# mother_board.net
KiCad netlist of a schematic drawn in Altium Designer
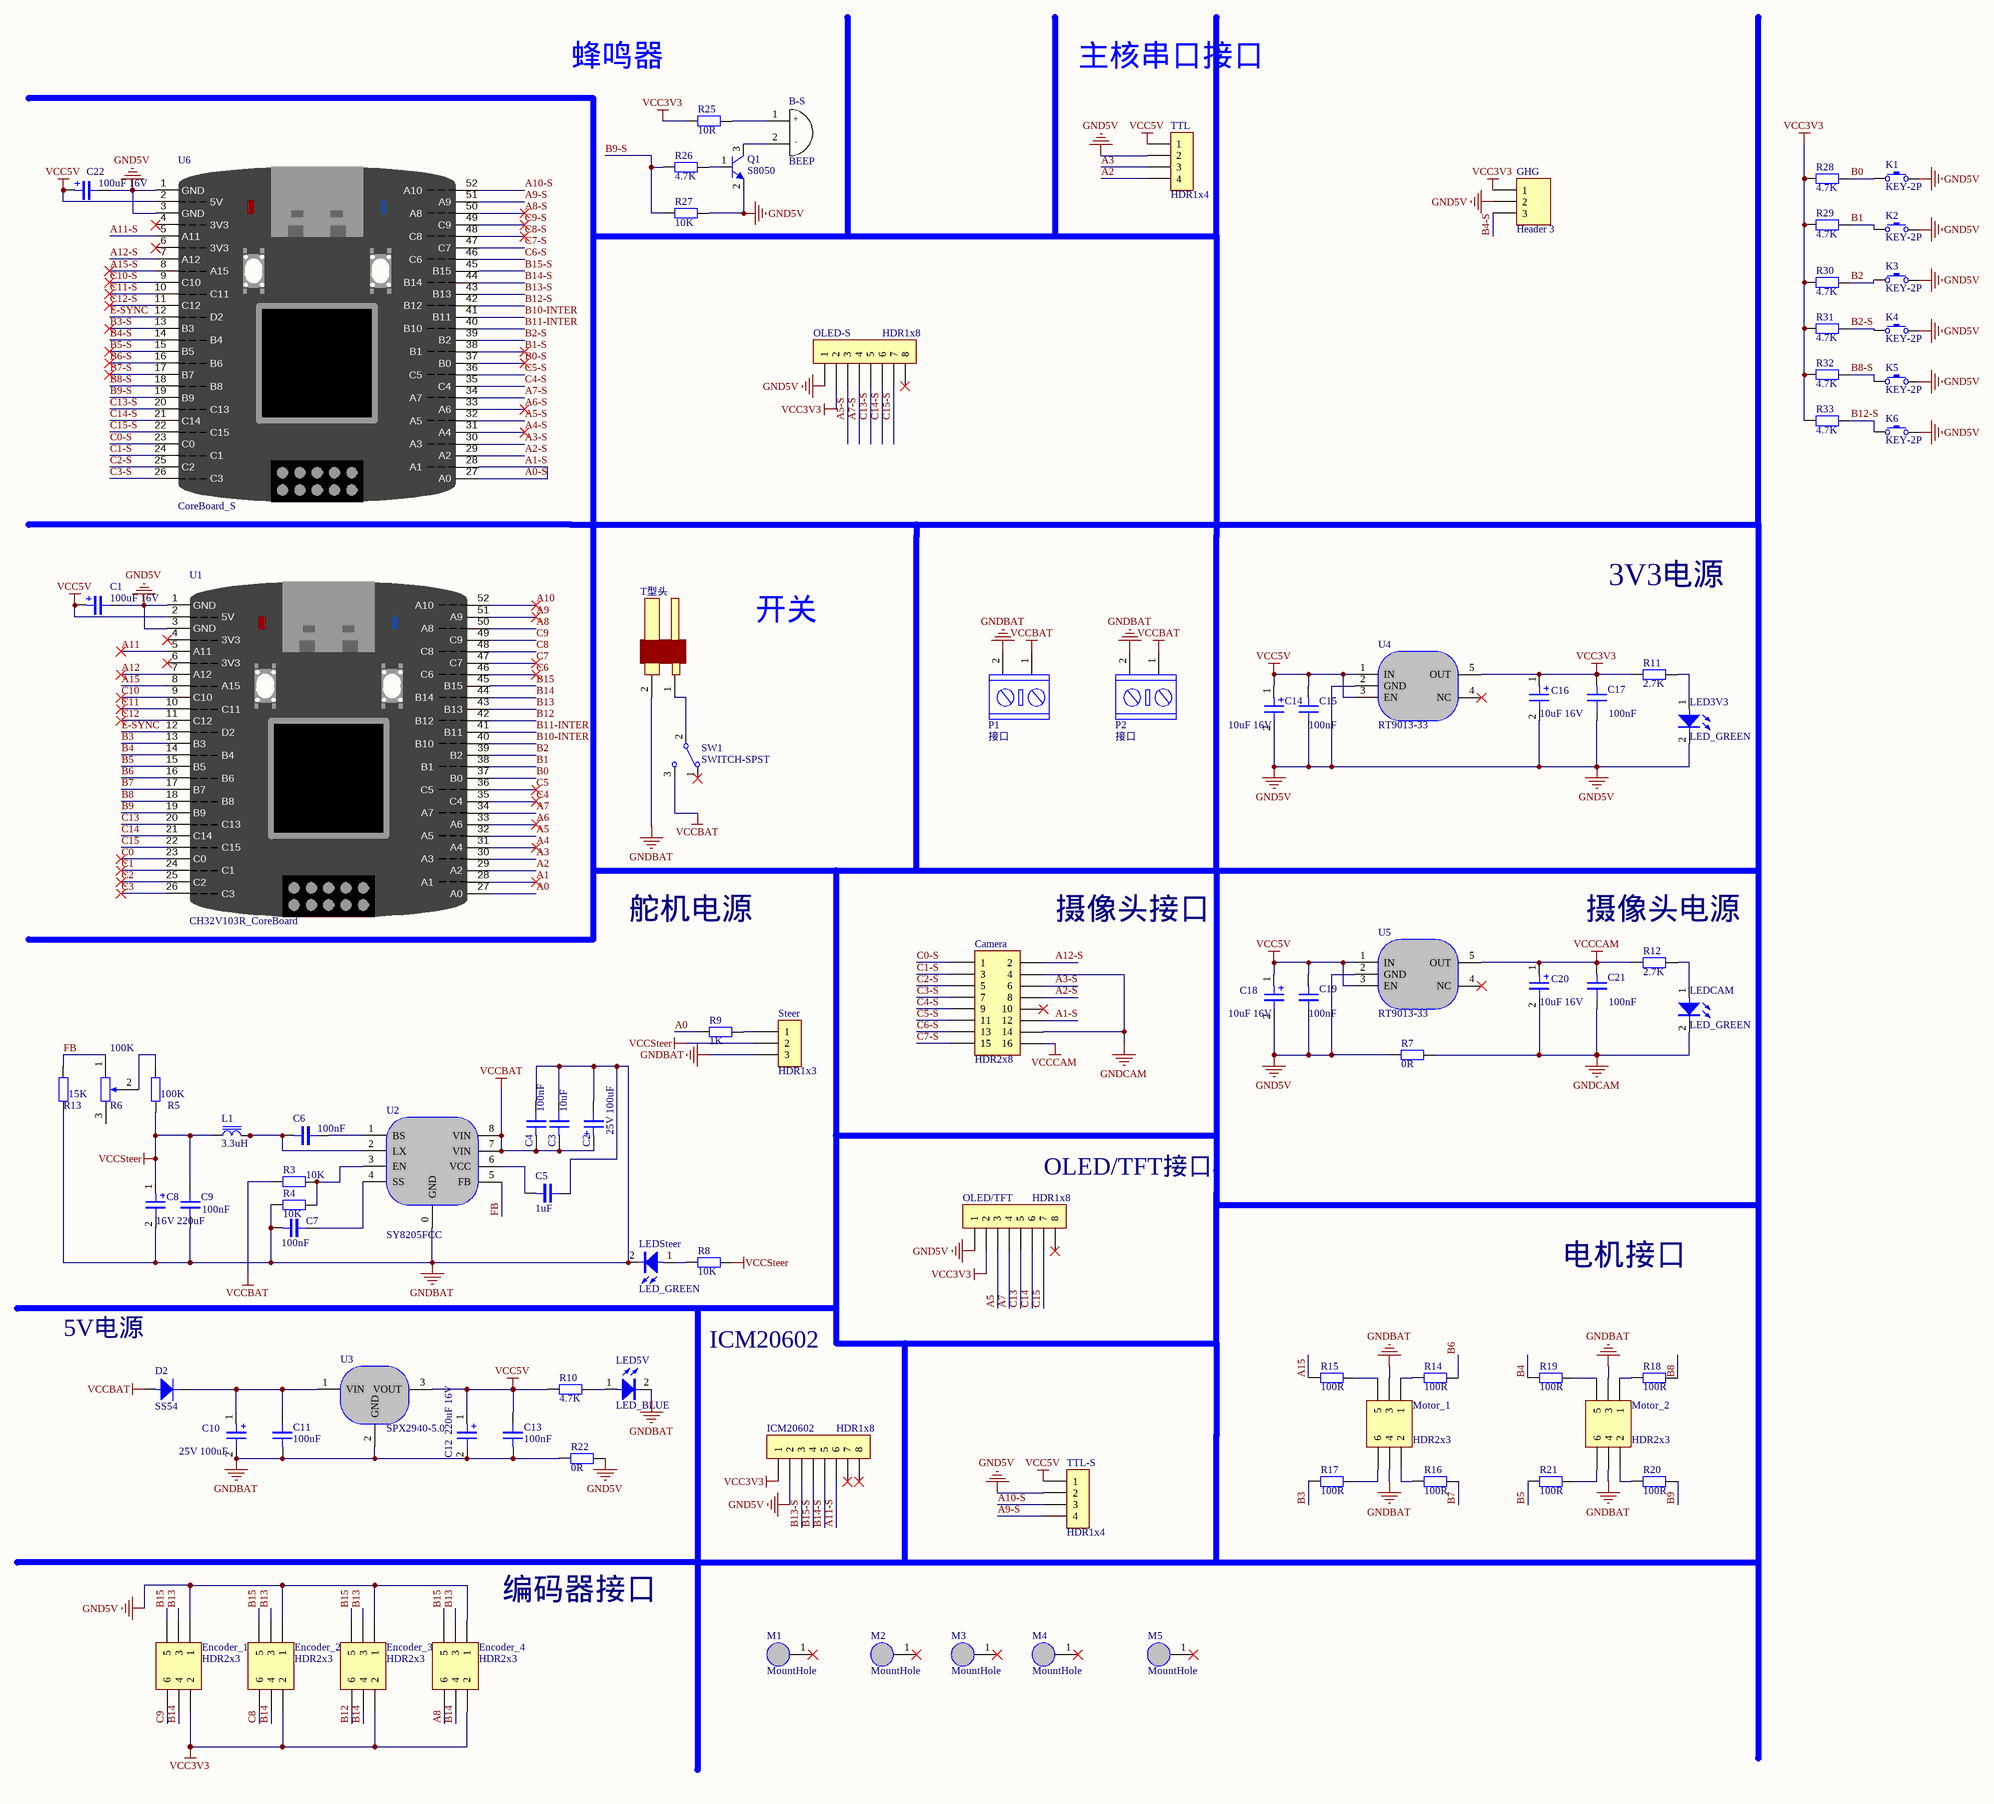
[diagram p0: mother_board.SchDoc]

(export (version "E")
  (design (tool "Eeschema 10.0.6"))
  (components
    (comp (ref "B-S")
      (value "BEEP")
      (footprint "BUZ-TH_BD9.0-P4.00-D1.0-FD")
      (libsource (lib "主板") (part "BEEP"))
    )
    (comp (ref "C1")
      (value "100uF 16V")
      (footprint "CASE-D_7343")
      (description "Tantalum Capacitor")
      (libsource (lib "主板") (part "CAP-TANTALUM"))
    )
    (comp (ref "C2")
      (value "25V 100uF")
      (footprint "SMD-ECAP-6.3x5.3")
      (description "Tantalum Capacitor")
      (libsource (lib "主板") (part "CAP-TANTALUM"))
    )
    (comp (ref "C3")
      (value "10uF")
      (footprint "0603_R")
      (description "Capacitor")
      (libsource (lib "主板") (part "CAP"))
    )
    (comp (ref "C4")
      (value "100nF")
      (footprint "0603_R")
      (description "Capacitor")
      (libsource (lib "主板") (part "CAP"))
    )
    (comp (ref "C5")
      (value "1uF")
      (footprint "0603_R")
      (description "Capacitor")
      (libsource (lib "主板") (part "CAP"))
    )
    (comp (ref "C6")
      (value "100nF")
      (footprint "0603_R")
      (description "Capacitor")
      (libsource (lib "主板") (part "CAP"))
    )
    (comp (ref "C7")
      (value "100nF")
      (footprint "0603_R")
      (description "Capacitor")
      (libsource (lib "主板") (part "CAP"))
    )
    (comp (ref "C8")
      (value "16V 220uF")
      (footprint "SMD-ECAP-6.3x5.3")
      (description "Tantalum Capacitor")
      (libsource (lib "") (part "CAP-TANTALUM_1"))
    )
    (comp (ref "C9")
      (value "100nF")
      (footprint "0603_R")
      (description "Capacitor")
      (libsource (lib "主板") (part "CAP"))
    )
    (comp (ref "C10")
      (value "25V 100uF")
      (footprint "SMD-ECAP-6.3x5.3")
      (description "Tantalum Capacitor")
      (libsource (lib "") (part "CAP-TANTALUM_1"))
    )
    (comp (ref "C11")
      (value "100nF")
      (footprint "0603_R")
      (description "Capacitor")
      (libsource (lib "主板") (part "CAP"))
    )
    (comp (ref "C12")
      (value "220uF 16V")
      (footprint "SMD-ECAP-6.3x5.3")
      (description "Tantalum Capacitor")
      (libsource (lib "") (part "CAP-TANTALUM_1"))
    )
    (comp (ref "C13")
      (value "100nF")
      (footprint "0603_R")
      (description "Capacitor")
      (libsource (lib "主板") (part "CAP"))
    )
    (comp (ref "C14")
      (value "10uF 16V")
      (footprint "CASE-A_3216")
      (description "Tantalum Capacitor")
      (libsource (lib "") (part "CAP-TANTALUM_1"))
    )
    (comp (ref "C15")
      (value "100nF")
      (footprint "0603_R")
      (description "Capacitor")
      (libsource (lib "主板") (part "CAP"))
    )
    (comp (ref "C16")
      (value "10uF 16V")
      (footprint "CASE-A_3216")
      (description "Tantalum Capacitor")
      (libsource (lib "") (part "CAP-TANTALUM_1"))
    )
    (comp (ref "C17")
      (value "100nF")
      (footprint "0603_R")
      (description "Capacitor")
      (libsource (lib "主板") (part "CAP"))
    )
    (comp (ref "C18")
      (value "10uF 16V")
      (footprint "CASE-A_3216")
      (description "Tantalum Capacitor")
      (libsource (lib "") (part "CAP-TANTALUM_1"))
    )
    (comp (ref "C19")
      (value "100nF")
      (footprint "0603_R")
      (description "Capacitor")
      (libsource (lib "主板") (part "CAP"))
    )
    (comp (ref "C20")
      (value "10uF 16V")
      (footprint "CASE-A_3216")
      (description "Tantalum Capacitor")
      (libsource (lib "") (part "CAP-TANTALUM_1"))
    )
    (comp (ref "C21")
      (value "100nF")
      (footprint "0603_R")
      (description "Capacitor")
      (libsource (lib "主板") (part "CAP"))
    )
    (comp (ref "C22")
      (value "100uF 16V")
      (footprint "CASE-D_7343")
      (description "Tantalum Capacitor")
      (libsource (lib "主板") (part "CAP-TANTALUM"))
    )
    (comp (ref "Camera")
      (value "HDR2x8")
      (footprint "HDR2X8")
      (description "Connector")
      (libsource (lib "主板") (part "HDR2x8"))
    )
    (comp (ref "D2")
      (value "SS54")
      (footprint "SMA(DO-214AC)_S1")
      (description "Schottky Diode")
      (libsource (lib "主板") (part "SS54"))
    )
    (comp (ref "Encoder_1")
      (value "HDR2x3")
      (footprint "HDR2X3")
      (description "Connector")
      (libsource (lib "主板") (part "HDR2x3"))
    )
    (comp (ref "Encoder_2")
      (value "HDR2x3")
      (footprint "HDR2X3")
      (description "Connector")
      (libsource (lib "主板") (part "HDR2x3"))
    )
    (comp (ref "Encoder_3")
      (value "HDR2x3")
      (footprint "HDR2X3")
      (description "Connector")
      (libsource (lib "主板") (part "HDR2x3"))
    )
    (comp (ref "Encoder_4")
      (value "HDR2x3")
      (footprint "HDR2X3")
      (description "Connector")
      (libsource (lib "主板") (part "HDR2x3"))
    )
    (comp (ref "GHG")
      (value "Header 3")
      (footprint "HDR1X3")
      (description "Header, 3-Pin")
      (fields (field (name "PUBLISHER") "Altium Limited"))
      (libsource (lib "Miscellaneous Connectors") (part "Header 3"))
    )
    (comp (ref "ICM20602")
      (value "HDR1x8")
      (footprint "HDR1X8")
      (description "Connector")
      (libsource (lib "主板") (part "HDR1x8"))
    )
    (comp (ref "K1")
      (value "KEY-2P")
      (footprint "SMD")
      (description "Key")
      (libsource (lib "主板") (part "KEY-2P"))
    )
    (comp (ref "K2")
      (value "KEY-2P")
      (footprint "SMD")
      (description "Key")
      (libsource (lib "主板") (part "KEY-2P"))
    )
    (comp (ref "K3")
      (value "KEY-2P")
      (footprint "SMD")
      (description "Key")
      (libsource (lib "主板") (part "KEY-2P"))
    )
    (comp (ref "K4")
      (value "KEY-2P")
      (footprint "SMD")
      (description "Key")
      (libsource (lib "主板") (part "KEY-2P"))
    )
    (comp (ref "K5")
      (value "KEY-2P")
      (footprint "SMD")
      (description "Key")
      (libsource (lib "主板") (part "KEY-2P"))
    )
    (comp (ref "K6")
      (value "KEY-2P")
      (footprint "SMD")
      (description "Key")
      (libsource (lib "主板") (part "KEY-2P"))
    )
    (comp (ref "L1") (value "3.3uH") (footprint "SMD-4.2x4.4x2.0") (libsource (lib "主板") (part "L?")))
    (comp (ref "LED3V3")
      (value "LED_GREEN")
      (footprint "0603-LED")
      (description "LED")
      (libsource (lib "主板") (part "LED"))
    )
    (comp (ref "LED5V")
      (value "LED_BLUE")
      (footprint "0603-LED")
      (description "LED")
      (libsource (lib "主板") (part "LED"))
    )
    (comp (ref "LEDCAM")
      (value "LED_GREEN")
      (footprint "0603-LED")
      (description "LED")
      (libsource (lib "主板") (part "LED"))
    )
    (comp (ref "LEDSteer")
      (value "LED_GREEN")
      (footprint "0603-LED")
      (description "LED")
      (libsource (lib "主板") (part "LED"))
    )
    (comp (ref "M1") (value "MountHole") (footprint "MountHole") (libsource (lib "主板") (part "MountHole")))
    (comp (ref "M2") (value "MountHole") (footprint "MountHole") (libsource (lib "主板") (part "MountHole")))
    (comp (ref "M3") (value "MountHole") (footprint "MountHole") (libsource (lib "主板") (part "MountHole")))
    (comp (ref "M4") (value "MountHole") (footprint "MountHole") (libsource (lib "主板") (part "MountHole")))
    (comp (ref "M5") (value "MountHole") (footprint "HOLE") (libsource (lib "主板") (part "MountHole")))
    (comp (ref "Motor_1")
      (value "HDR2x3")
      (footprint "HDR2X3")
      (description "Connector")
      (libsource (lib "主板") (part "HDR2x3"))
    )
    (comp (ref "Motor_2")
      (value "HDR2x3")
      (footprint "HDR2X3")
      (description "Connector")
      (libsource (lib "主板") (part "HDR2x3"))
    )
    (comp (ref "OLED-S")
      (value "HDR1x8")
      (footprint "HDR1X8")
      (description "Connector")
      (libsource (lib "主板") (part "HDR1x8"))
    )
    (comp (ref "OLED/TFT")
      (value "HDR1x8")
      (footprint "HDR1X8")
      (description "Connector")
      (libsource (lib "主板") (part "HDR1x8"))
    )
    (comp (ref "P1") (value "接口") (footprint "KF/WJ/DG 301-2p-5.0mm") (libsource (lib "主板") (part "接口")))
    (comp (ref "P2") (value "接口") (footprint "KF/WJ/DG 301-2p-5.0mm") (libsource (lib "主板") (part "接口")))
    (comp (ref "Q1")
      (value "S8050")
      (footprint "SOT-23(SOT-23-3)")
      (description "NPN Bipolar Transistor")
      (libsource (lib "主板") (part "S8050"))
    )
    (comp (ref "R3")
      (value "10K")
      (footprint "0603_L")
      (description "Resistor")
      (libsource (lib "主板") (part "RES"))
    )
    (comp (ref "R4")
      (value "10K")
      (footprint "0603_L")
      (description "Resistor")
      (libsource (lib "主板") (part "RES"))
    )
    (comp (ref "R5")
      (value "100K")
      (footprint "0603_L")
      (description "Resistor")
      (libsource (lib "") (part "RES_1"))
    )
    (comp (ref "R6")
      (value "100K")
      (footprint "3296W")
      (description "注意核对封装引脚")
      (libsource (lib "主板") (part "RES-CHANGABLE"))
    )
    (comp (ref "R7")
      (value "0R")
      (footprint "0603_L")
      (description "Resistor")
      (libsource (lib "主板") (part "RES"))
    )
    (comp (ref "R8")
      (value "10K")
      (footprint "0603_L")
      (description "Resistor")
      (libsource (lib "主板") (part "RES"))
    )
    (comp (ref "R9")
      (value "1K")
      (footprint "0603_L")
      (description "Resistor")
      (libsource (lib "主板") (part "RES"))
    )
    (comp (ref "R10")
      (value "4.7K")
      (footprint "0603_L")
      (description "Resistor")
      (libsource (lib "主板") (part "RES"))
    )
    (comp (ref "R11")
      (value "2.7K")
      (footprint "0603_L")
      (description "Resistor")
      (libsource (lib "主板") (part "RES"))
    )
    (comp (ref "R12")
      (value "2.7K")
      (footprint "0603_L")
      (description "Resistor")
      (libsource (lib "主板") (part "RES"))
    )
    (comp (ref "R13")
      (value "15K")
      (footprint "0603_L")
      (description "Resistor")
      (libsource (lib "") (part "RES_1"))
    )
    (comp (ref "R14")
      (value "100R")
      (footprint "0603_L")
      (description "Resistor")
      (libsource (lib "主板") (part "RES"))
    )
    (comp (ref "R15")
      (value "100R")
      (footprint "0603_L")
      (description "Resistor")
      (libsource (lib "主板") (part "RES"))
    )
    (comp (ref "R16")
      (value "100R")
      (footprint "0603_L")
      (description "Resistor")
      (libsource (lib "主板") (part "RES"))
    )
    (comp (ref "R17")
      (value "100R")
      (footprint "0603_L")
      (description "Resistor")
      (libsource (lib "主板") (part "RES"))
    )
    (comp (ref "R18")
      (value "100R")
      (footprint "0603_L")
      (description "Resistor")
      (libsource (lib "主板") (part "RES"))
    )
    (comp (ref "R19")
      (value "100R")
      (footprint "0603_L")
      (description "Resistor")
      (libsource (lib "主板") (part "RES"))
    )
    (comp (ref "R20")
      (value "100R")
      (footprint "0603_L")
      (description "Resistor")
      (libsource (lib "主板") (part "RES"))
    )
    (comp (ref "R21")
      (value "100R")
      (footprint "0603_L")
      (description "Resistor")
      (libsource (lib "主板") (part "RES"))
    )
    (comp (ref "R22")
      (value "0R")
      (footprint "0603_L")
      (description "Resistor")
      (libsource (lib "主板") (part "RES"))
    )
    (comp (ref "R25")
      (value "10R")
      (footprint "0603_L")
      (description "Resistor")
      (libsource (lib "主板") (part "RES"))
    )
    (comp (ref "R26")
      (value "4.7K")
      (footprint "0603_L")
      (description "Resistor")
      (libsource (lib "主板") (part "RES"))
    )
    (comp (ref "R27")
      (value "10K")
      (footprint "0603_L")
      (description "Resistor")
      (libsource (lib "主板") (part "RES"))
    )
    (comp (ref "R28")
      (value "4.7K")
      (footprint "0603_L")
      (description "Resistor")
      (libsource (lib "主板") (part "RES"))
    )
    (comp (ref "R29")
      (value "4.7K")
      (footprint "0603_L")
      (description "Resistor")
      (libsource (lib "主板") (part "RES"))
    )
    (comp (ref "R30")
      (value "4.7K")
      (footprint "0603_L")
      (description "Resistor")
      (libsource (lib "主板") (part "RES"))
    )
    (comp (ref "R31")
      (value "4.7K")
      (footprint "0603_L")
      (description "Resistor")
      (libsource (lib "主板") (part "RES"))
    )
    (comp (ref "R32")
      (value "4.7K")
      (footprint "0603_L")
      (description "Resistor")
      (libsource (lib "主板") (part "RES"))
    )
    (comp (ref "R33")
      (value "4.7K")
      (footprint "0603_L")
      (description "Resistor")
      (libsource (lib "主板") (part "RES"))
    )
    (comp (ref "Steer")
      (value "HDR1x3")
      (footprint "HDR1X3")
      (description "Connector")
      (libsource (lib "主板") (part "HDR1x3"))
    )
    (comp (ref "SW1")
      (value "SWITCH-SPST")
      (footprint "ToggleSwitch 7102")
      (description "Switch")
      (libsource (lib "主板") (part "SWITCH-SPST"))
    )
    (comp (ref "TTL")
      (value "HDR1x4")
      (footprint "HDR1X4")
      (description "Connector")
      (libsource (lib "主板") (part "HDR1x4"))
    )
    (comp (ref "TTL-S")
      (value "HDR1x4")
      (footprint "HDR1X4")
      (description "Connector")
      (libsource (lib "主板") (part "HDR1x4"))
    )
    (comp (ref "T型头") (value "T型头") (footprint "T型头焊盘") (libsource (lib "主板") (part "T型头")))
    (comp (ref "U1")
      (value "CH32V103R_CoreBoard")
      (footprint "CH32V103R_CoreBoard")
      (description "逐飞科技 CH32V103R核心板")
      (libsource (lib "主板") (part "CH32V103R_CoreBoard"))
    )
    (comp (ref "U2")
      (value "SY8205FCC")
      (footprint "SOIC-8_EP_150mil")
      (libsource (lib "主板") (part "SY8205FCC"))
    )
    (comp (ref "U3") (value "SPX2940-5.0") (footprint "TO-263-3") (libsource (lib "主板") (part "SPX2940-5.0")))
    (comp (ref "U4") (value "RT9013-33") (footprint "SOT-23-5") (libsource (lib "主板") (part "RT9013-33")))
    (comp (ref "U5") (value "RT9013-33") (footprint "SOT-23-5") (libsource (lib "主板") (part "RT9013-33")))
    (comp (ref "U6")
      (value "CoreBoard_S")
      (footprint "CH32V103R_CoreBoard")
      (description "逐飞科技 CH32V103R核心板")
      (libsource (lib "主板") (part "CH32V103R_CoreBoard"))
    )
  )
  (nets
    (net (code "1") (name "/A0") (class "Default")
      (node (ref "R9") (pin "1") (pinfunction "1_1") (pintype "passive"))
      (node (ref "U1") (pin "27") (pinfunction "A0_27") (pintype "passive"))
    )
    (net (code "2") (name "/A0-S") (class "Default")
      (node (ref "Camera") (pin "12") (pinfunction "12_12") (pintype "passive"))
      (node (ref "U6") (pin "27") (pinfunction "A0_27") (pintype "passive"))
      (node (ref "U6") (pin "28") (pinfunction "A1_28") (pintype "passive"))
    )
    (net (code "3") (name "/A1") (class "Default")
      (node (ref "U1") (pin "28") (pinfunction "A1_28") (pintype "passive+no_connect"))
    )
    (net (code "4") (name "/A2") (class "Default")
      (node (ref "TTL") (pin "4") (pinfunction "4_4") (pintype "passive"))
      (node (ref "U1") (pin "29") (pinfunction "A2_29") (pintype "passive"))
    )
    (net (code "5") (name "/A2-S") (class "Default")
      (node (ref "Camera") (pin "8") (pinfunction "8_8") (pintype "passive"))
      (node (ref "U6") (pin "29") (pinfunction "A2_29") (pintype "passive"))
    )
    (net (code "6") (name "/A3") (class "Default")
      (node (ref "TTL") (pin "3") (pinfunction "3_3") (pintype "passive"))
      (node (ref "U1") (pin "30") (pinfunction "A3_30") (pintype "passive"))
    )
    (net (code "7") (name "/A3-S") (class "Default")
      (node (ref "Camera") (pin "6") (pinfunction "6_6") (pintype "passive"))
      (node (ref "U6") (pin "30") (pinfunction "A3_30") (pintype "passive"))
    )
    (net (code "8") (name "/A4") (class "Default")
      (node (ref "U1") (pin "31") (pinfunction "A4_31") (pintype "passive+no_connect"))
    )
    (net (code "9") (name "/A4-S") (class "Default")
      (node (ref "U6") (pin "31") (pinfunction "A4_31") (pintype "passive+no_connect"))
    )
    (net (code "10") (name "/A5") (class "Default")
      (node (ref "OLED/TFT") (pin "3") (pinfunction "3_3") (pintype "passive"))
      (node (ref "U1") (pin "32") (pinfunction "A5_32") (pintype "passive"))
    )
    (net (code "11") (name "/A5-S") (class "Default")
      (node (ref "OLED-S") (pin "3") (pinfunction "3_3") (pintype "passive"))
      (node (ref "U6") (pin "32") (pinfunction "A5_32") (pintype "passive"))
    )
    (net (code "12") (name "/A6") (class "Default")
      (node (ref "U1") (pin "33") (pinfunction "A6_33") (pintype "passive+no_connect"))
    )
    (net (code "13") (name "/A6-S") (class "Default")
      (node (ref "U6") (pin "33") (pinfunction "A6_33") (pintype "passive+no_connect"))
    )
    (net (code "14") (name "/A7") (class "Default")
      (node (ref "OLED/TFT") (pin "4") (pinfunction "4_4") (pintype "passive"))
      (node (ref "U1") (pin "34") (pinfunction "A7_34") (pintype "passive"))
    )
    (net (code "15") (name "/A7-S") (class "Default")
      (node (ref "OLED-S") (pin "4") (pinfunction "4_4") (pintype "passive"))
      (node (ref "U6") (pin "34") (pinfunction "A7_34") (pintype "passive"))
    )
    (net (code "16") (name "/A8") (class "Default")
      (node (ref "Encoder_4") (pin "6") (pinfunction "6_6") (pintype "passive"))
      (node (ref "U1") (pin "50") (pinfunction "A8_50") (pintype "passive"))
    )
    (net (code "17") (name "/A8-S") (class "Default")
      (node (ref "U6") (pin "50") (pinfunction "A8_50") (pintype "passive+no_connect"))
    )
    (net (code "18") (name "/A9") (class "Default")
      (node (ref "U1") (pin "51") (pinfunction "A9_51") (pintype "passive+no_connect"))
    )
    (net (code "19") (name "/A9-S") (class "Default")
      (node (ref "TTL-S") (pin "4") (pinfunction "4_4") (pintype "passive"))
      (node (ref "U6") (pin "51") (pinfunction "A9_51") (pintype "passive"))
    )
    (net (code "20") (name "/A10") (class "Default")
      (node (ref "U1") (pin "52") (pinfunction "A10_52") (pintype "passive+no_connect"))
    )
    (net (code "21") (name "/A10-S") (class "Default")
      (node (ref "TTL-S") (pin "3") (pinfunction "3_3") (pintype "passive"))
      (node (ref "U6") (pin "52") (pinfunction "A10_52") (pintype "passive"))
    )
    (net (code "22") (name "/A11") (class "Default")
      (node (ref "U1") (pin "5") (pinfunction "A11_5") (pintype "passive+no_connect"))
    )
    (net (code "23") (name "/A11-S") (class "Default")
      (node (ref "ICM20602") (pin "6") (pinfunction "6_6") (pintype "passive"))
      (node (ref "U6") (pin "5") (pinfunction "A11_5") (pintype "passive"))
    )
    (net (code "24") (name "/A12") (class "Default")
      (node (ref "U1") (pin "7") (pinfunction "A12_7") (pintype "passive+no_connect"))
    )
    (net (code "25") (name "/A12-S") (class "Default")
      (node (ref "Camera") (pin "2") (pinfunction "2_2") (pintype "passive"))
      (node (ref "U6") (pin "7") (pinfunction "A12_7") (pintype "passive"))
    )
    (net (code "26") (name "/A15") (class "Default")
      (node (ref "R15") (pin "1") (pinfunction "1_1") (pintype "passive"))
      (node (ref "U1") (pin "8") (pinfunction "A15_8") (pintype "passive"))
    )
    (net (code "27") (name "/A15-S") (class "Default")
      (node (ref "U6") (pin "8") (pinfunction "A15_8") (pintype "passive+no_connect"))
    )
    (net (code "28") (name "/B0") (class "Default")
      (node (ref "K1") (pin "1") (pinfunction "1_1") (pintype "passive"))
      (node (ref "R28") (pin "2") (pinfunction "2_2") (pintype "passive"))
      (node (ref "U1") (pin "37") (pinfunction "B0_37") (pintype "passive"))
    )
    (net (code "29") (name "/B0-S") (class "Default")
      (node (ref "U6") (pin "37") (pinfunction "B0_37") (pintype "passive+no_connect"))
    )
    (net (code "30") (name "/B1") (class "Default")
      (node (ref "K2") (pin "1") (pinfunction "1_1") (pintype "passive"))
      (node (ref "R29") (pin "2") (pinfunction "2_2") (pintype "passive"))
      (node (ref "U1") (pin "38") (pinfunction "B1_38") (pintype "passive"))
    )
    (net (code "31") (name "/B1-S") (class "Default")
      (node (ref "U6") (pin "38") (pinfunction "B1_38") (pintype "passive+no_connect"))
    )
    (net (code "32") (name "/B2") (class "Default")
      (node (ref "K3") (pin "1") (pinfunction "1_1") (pintype "passive"))
      (node (ref "R30") (pin "2") (pinfunction "2_2") (pintype "passive"))
      (node (ref "U1") (pin "39") (pinfunction "B2_39") (pintype "passive"))
    )
    (net (code "33") (name "/B2-S") (class "Default")
      (node (ref "K4") (pin "1") (pinfunction "1_1") (pintype "passive"))
      (node (ref "R31") (pin "2") (pinfunction "2_2") (pintype "passive"))
      (node (ref "U6") (pin "39") (pinfunction "B2_39") (pintype "passive"))
    )
    (net (code "34") (name "/B3") (class "Default")
      (node (ref "R17") (pin "1") (pinfunction "1_1") (pintype "passive"))
      (node (ref "U1") (pin "13") (pinfunction "B3_13") (pintype "passive"))
    )
    (net (code "35") (name "/B3-S") (class "Default")
      (node (ref "U6") (pin "13") (pinfunction "B3_13") (pintype "passive+no_connect"))
    )
    (net (code "36") (name "/B4") (class "Default")
      (node (ref "R19") (pin "1") (pinfunction "1_1") (pintype "passive"))
      (node (ref "U1") (pin "14") (pinfunction "B4_14") (pintype "passive"))
    )
    (net (code "37") (name "/B4-S") (class "Default")
      (node (ref "GHG") (pin "3") (pinfunction "3_3") (pintype "passive"))
      (node (ref "U6") (pin "14") (pinfunction "B4_14") (pintype "passive"))
    )
    (net (code "38") (name "/B5") (class "Default")
      (node (ref "R21") (pin "1") (pinfunction "1_1") (pintype "passive"))
      (node (ref "U1") (pin "15") (pinfunction "B5_15") (pintype "passive"))
    )
    (net (code "39") (name "/B5-S") (class "Default")
      (node (ref "U6") (pin "15") (pinfunction "B5_15") (pintype "passive+no_connect"))
    )
    (net (code "40") (name "/B6") (class "Default")
      (node (ref "R14") (pin "2") (pinfunction "2_2") (pintype "passive"))
      (node (ref "U1") (pin "16") (pinfunction "B6_16") (pintype "passive"))
    )
    (net (code "41") (name "/B6-S") (class "Default")
      (node (ref "U6") (pin "16") (pinfunction "B6_16") (pintype "passive+no_connect"))
    )
    (net (code "42") (name "/B7") (class "Default")
      (node (ref "R16") (pin "2") (pinfunction "2_2") (pintype "passive"))
      (node (ref "U1") (pin "17") (pinfunction "B7_17") (pintype "passive"))
    )
    (net (code "43") (name "/B7-S") (class "Default")
      (node (ref "U6") (pin "17") (pinfunction "B7_17") (pintype "passive+no_connect"))
    )
    (net (code "44") (name "/B8") (class "Default")
      (node (ref "R18") (pin "2") (pinfunction "2_2") (pintype "passive"))
      (node (ref "U1") (pin "18") (pinfunction "B8_18") (pintype "passive"))
    )
    (net (code "45") (name "/B8-S") (class "Default")
      (node (ref "K5") (pin "1") (pinfunction "1_1") (pintype "passive"))
      (node (ref "R32") (pin "2") (pinfunction "2_2") (pintype "passive"))
      (node (ref "U6") (pin "18") (pinfunction "B8_18") (pintype "passive"))
    )
    (net (code "46") (name "/B9") (class "Default")
      (node (ref "R20") (pin "2") (pinfunction "2_2") (pintype "passive"))
      (node (ref "U1") (pin "19") (pinfunction "B9_19") (pintype "passive"))
    )
    (net (code "47") (name "/B9-S") (class "Default")
      (node (ref "R26") (pin "1") (pinfunction "1_1") (pintype "passive"))
      (node (ref "R27") (pin "1") (pinfunction "1_1") (pintype "passive"))
      (node (ref "U6") (pin "19") (pinfunction "B9_19") (pintype "passive"))
    )
    (net (code "48") (name "/B10-INTER") (class "Default")
      (node (ref "U1") (pin "40") (pinfunction "B10_40") (pintype "passive"))
      (node (ref "U6") (pin "41") (pinfunction "B11_41") (pintype "passive"))
    )
    (net (code "49") (name "/B11-INTER") (class "Default")
      (node (ref "U1") (pin "41") (pinfunction "B11_41") (pintype "passive"))
      (node (ref "U6") (pin "40") (pinfunction "B10_40") (pintype "passive"))
    )
    (net (code "50") (name "/B12") (class "Default")
      (node (ref "Encoder_3") (pin "6") (pinfunction "6_6") (pintype "passive"))
      (node (ref "U1") (pin "42") (pinfunction "B12_42") (pintype "passive"))
    )
    (net (code "51") (name "/B12-S") (class "Default")
      (node (ref "K6") (pin "1") (pinfunction "1_1") (pintype "passive"))
      (node (ref "R33") (pin "2") (pinfunction "2_2") (pintype "passive"))
      (node (ref "U6") (pin "42") (pinfunction "B12_42") (pintype "passive"))
    )
    (net (code "52") (name "/B13") (class "Default")
      (node (ref "Encoder_1") (pin "3") (pinfunction "3_3") (pintype "passive"))
      (node (ref "Encoder_2") (pin "3") (pinfunction "3_3") (pintype "passive"))
      (node (ref "Encoder_3") (pin "3") (pinfunction "3_3") (pintype "passive"))
      (node (ref "Encoder_4") (pin "3") (pinfunction "3_3") (pintype "passive"))
      (node (ref "U1") (pin "43") (pinfunction "B13_43") (pintype "passive"))
    )
    (net (code "53") (name "/B13-S") (class "Default")
      (node (ref "ICM20602") (pin "3") (pinfunction "3_3") (pintype "passive"))
      (node (ref "U6") (pin "43") (pinfunction "B13_43") (pintype "passive"))
    )
    (net (code "54") (name "/B14") (class "Default")
      (node (ref "Encoder_1") (pin "4") (pinfunction "4_4") (pintype "passive"))
      (node (ref "Encoder_2") (pin "4") (pinfunction "4_4") (pintype "passive"))
      (node (ref "Encoder_3") (pin "4") (pinfunction "4_4") (pintype "passive"))
      (node (ref "Encoder_4") (pin "4") (pinfunction "4_4") (pintype "passive"))
      (node (ref "U1") (pin "44") (pinfunction "B14_44") (pintype "passive"))
    )
    (net (code "55") (name "/B14-S") (class "Default")
      (node (ref "ICM20602") (pin "5") (pinfunction "5_5") (pintype "passive"))
      (node (ref "U6") (pin "44") (pinfunction "B14_44") (pintype "passive"))
    )
    (net (code "56") (name "/B15") (class "Default")
      (node (ref "Encoder_1") (pin "5") (pinfunction "5_5") (pintype "passive"))
      (node (ref "Encoder_2") (pin "5") (pinfunction "5_5") (pintype "passive"))
      (node (ref "Encoder_3") (pin "5") (pinfunction "5_5") (pintype "passive"))
      (node (ref "Encoder_4") (pin "5") (pinfunction "5_5") (pintype "passive"))
      (node (ref "U1") (pin "45") (pinfunction "B15_45") (pintype "passive"))
    )
    (net (code "57") (name "/B15-S") (class "Default")
      (node (ref "ICM20602") (pin "4") (pinfunction "4_4") (pintype "passive"))
      (node (ref "U6") (pin "45") (pinfunction "B15_45") (pintype "passive"))
    )
    (net (code "58") (name "/C0") (class "Default")
      (node (ref "U1") (pin "23") (pinfunction "C0_23") (pintype "passive+no_connect"))
    )
    (net (code "59") (name "/C0-S") (class "Default")
      (node (ref "Camera") (pin "1") (pinfunction "1_1") (pintype "passive"))
      (node (ref "U6") (pin "23") (pinfunction "C0_23") (pintype "passive"))
    )
    (net (code "60") (name "/C1") (class "Default")
      (node (ref "U1") (pin "24") (pinfunction "C1_24") (pintype "passive+no_connect"))
    )
    (net (code "61") (name "/C1-S") (class "Default")
      (node (ref "Camera") (pin "3") (pinfunction "3_3") (pintype "passive"))
      (node (ref "U6") (pin "24") (pinfunction "C1_24") (pintype "passive"))
    )
    (net (code "62") (name "/C2") (class "Default")
      (node (ref "U1") (pin "25") (pinfunction "C2_25") (pintype "passive+no_connect"))
    )
    (net (code "63") (name "/C2-S") (class "Default")
      (node (ref "Camera") (pin "5") (pinfunction "5_5") (pintype "passive"))
      (node (ref "U6") (pin "25") (pinfunction "C2_25") (pintype "passive"))
    )
    (net (code "64") (name "/C3") (class "Default")
      (node (ref "U1") (pin "26") (pinfunction "C3_26") (pintype "passive+no_connect"))
    )
    (net (code "65") (name "/C3-S") (class "Default")
      (node (ref "Camera") (pin "7") (pinfunction "7_7") (pintype "passive"))
      (node (ref "U6") (pin "26") (pinfunction "C3_26") (pintype "passive"))
    )
    (net (code "66") (name "/C4") (class "Default")
      (node (ref "U1") (pin "35") (pinfunction "C4_35") (pintype "passive+no_connect"))
    )
    (net (code "67") (name "/C4-S") (class "Default")
      (node (ref "Camera") (pin "9") (pinfunction "9_9") (pintype "passive"))
      (node (ref "U6") (pin "35") (pinfunction "C4_35") (pintype "passive"))
    )
    (net (code "68") (name "/C5") (class "Default")
      (node (ref "U1") (pin "36") (pinfunction "C5_36") (pintype "passive+no_connect"))
    )
    (net (code "69") (name "/C5-S") (class "Default")
      (node (ref "Camera") (pin "11") (pinfunction "11_11") (pintype "passive"))
      (node (ref "U6") (pin "36") (pinfunction "C5_36") (pintype "passive"))
    )
    (net (code "70") (name "/C6") (class "Default")
      (node (ref "U1") (pin "46") (pinfunction "C6_46") (pintype "passive+no_connect"))
    )
    (net (code "71") (name "/C6-S") (class "Default")
      (node (ref "Camera") (pin "13") (pinfunction "13_13") (pintype "passive"))
      (node (ref "U6") (pin "46") (pinfunction "C6_46") (pintype "passive"))
    )
    (net (code "72") (name "/C7") (class "Default")
      (node (ref "U1") (pin "47") (pinfunction "C7_47") (pintype "passive+no_connect"))
    )
    (net (code "73") (name "/C7-S") (class "Default")
      (node (ref "Camera") (pin "15") (pinfunction "15_15") (pintype "passive"))
      (node (ref "U6") (pin "47") (pinfunction "C7_47") (pintype "passive"))
    )
    (net (code "74") (name "/C8") (class "Default")
      (node (ref "Encoder_2") (pin "6") (pinfunction "6_6") (pintype "passive"))
      (node (ref "U1") (pin "48") (pinfunction "C8_48") (pintype "passive"))
    )
    (net (code "75") (name "/C8-S") (class "Default")
      (node (ref "U6") (pin "48") (pinfunction "C8_48") (pintype "passive+no_connect"))
    )
    (net (code "76") (name "/C9") (class "Default")
      (node (ref "Encoder_1") (pin "6") (pinfunction "6_6") (pintype "passive"))
      (node (ref "U1") (pin "49") (pinfunction "C9_49") (pintype "passive"))
    )
    (net (code "77") (name "/C9-S") (class "Default")
      (node (ref "U6") (pin "49") (pinfunction "C9_49") (pintype "passive+no_connect"))
    )
    (net (code "78") (name "/C10") (class "Default")
      (node (ref "U1") (pin "9") (pinfunction "C10_9") (pintype "passive+no_connect"))
    )
    (net (code "79") (name "/C10-S") (class "Default")
      (node (ref "U6") (pin "9") (pinfunction "C10_9") (pintype "passive+no_connect"))
    )
    (net (code "80") (name "/C11") (class "Default")
      (node (ref "U1") (pin "10") (pinfunction "C11_10") (pintype "passive+no_connect"))
    )
    (net (code "81") (name "/C11-S") (class "Default")
      (node (ref "U6") (pin "10") (pinfunction "C11_10") (pintype "passive+no_connect"))
    )
    (net (code "82") (name "/C12") (class "Default")
      (node (ref "U1") (pin "11") (pinfunction "C12_11") (pintype "passive+no_connect"))
    )
    (net (code "83") (name "/C12-S") (class "Default")
      (node (ref "U6") (pin "11") (pinfunction "C12_11") (pintype "passive+no_connect"))
    )
    (net (code "84") (name "/C13") (class "Default")
      (node (ref "OLED/TFT") (pin "5") (pinfunction "5_5") (pintype "passive"))
      (node (ref "U1") (pin "20") (pinfunction "C13_20") (pintype "passive"))
    )
    (net (code "85") (name "/C13-S") (class "Default")
      (node (ref "OLED-S") (pin "5") (pinfunction "5_5") (pintype "passive"))
      (node (ref "U6") (pin "20") (pinfunction "C13_20") (pintype "passive"))
    )
    (net (code "86") (name "/C14") (class "Default")
      (node (ref "OLED/TFT") (pin "6") (pinfunction "6_6") (pintype "passive"))
      (node (ref "U1") (pin "21") (pinfunction "C14_21") (pintype "passive"))
    )
    (net (code "87") (name "/C14-S") (class "Default")
      (node (ref "OLED-S") (pin "6") (pinfunction "6_6") (pintype "passive"))
      (node (ref "U6") (pin "21") (pinfunction "C14_21") (pintype "passive"))
    )
    (net (code "88") (name "/C15") (class "Default")
      (node (ref "OLED/TFT") (pin "7") (pinfunction "7_7") (pintype "passive"))
      (node (ref "U1") (pin "22") (pinfunction "C15_22") (pintype "passive"))
    )
    (net (code "89") (name "/C15-S") (class "Default")
      (node (ref "OLED-S") (pin "7") (pinfunction "7_7") (pintype "passive"))
      (node (ref "U6") (pin "22") (pinfunction "C15_22") (pintype "passive"))
    )
    (net (code "90") (name "/E-SYNC") (class "Default")
      (node (ref "U1") (pin "12") (pinfunction "D2_12") (pintype "passive"))
      (node (ref "U6") (pin "12") (pinfunction "D2_12") (pintype "passive"))
    )
    (net (code "91") (name "/FB") (class "Default")
      (node (ref "R13") (pin "1") (pinfunction "1_1") (pintype "passive"))
      (node (ref "R6") (pin "1") (pinfunction "1_1") (pintype "passive"))
      (node (ref "U2") (pin "5") (pinfunction "FB_5") (pintype "passive"))
    )
    (net (code "92") (name "GND5V") (class "Default")
      (node (ref "C1") (pin "2") (pinfunction "2_2") (pintype "passive"))
      (node (ref "C14") (pin "2") (pinfunction "2_2") (pintype "passive"))
      (node (ref "C15") (pin "2") (pinfunction "2_2") (pintype "passive"))
      (node (ref "C16") (pin "2") (pinfunction "2_2") (pintype "passive"))
      (node (ref "C17") (pin "2") (pinfunction "2_2") (pintype "passive"))
      (node (ref "C18") (pin "2") (pinfunction "2_2") (pintype "passive"))
      (node (ref "C19") (pin "2") (pinfunction "2_2") (pintype "passive"))
      (node (ref "C22") (pin "2") (pinfunction "2_2") (pintype "passive"))
      (node (ref "Encoder_1") (pin "1") (pinfunction "1_1") (pintype "passive"))
      (node (ref "Encoder_2") (pin "1") (pinfunction "1_1") (pintype "passive"))
      (node (ref "Encoder_3") (pin "1") (pinfunction "1_1") (pintype "passive"))
      (node (ref "Encoder_4") (pin "1") (pinfunction "1_1") (pintype "passive"))
      (node (ref "GHG") (pin "2") (pinfunction "2_2") (pintype "passive"))
      (node (ref "ICM20602") (pin "2") (pinfunction "2_2") (pintype "passive"))
      (node (ref "K1") (pin "2") (pinfunction "2_2") (pintype "passive"))
      (node (ref "K2") (pin "2") (pinfunction "2_2") (pintype "passive"))
      (node (ref "K3") (pin "2") (pinfunction "2_2") (pintype "passive"))
      (node (ref "K4") (pin "2") (pinfunction "2_2") (pintype "passive"))
      (node (ref "K5") (pin "2") (pinfunction "2_2") (pintype "passive"))
      (node (ref "K6") (pin "2") (pinfunction "2_2") (pintype "passive"))
      (node (ref "LED3V3") (pin "2") (pinfunction "C_2") (pintype "passive"))
      (node (ref "OLED-S") (pin "1") (pinfunction "1_1") (pintype "passive"))
      (node (ref "OLED/TFT") (pin "1") (pinfunction "1_1") (pintype "passive"))
      (node (ref "Q1") (pin "2") (pinfunction "E_2") (pintype "passive"))
      (node (ref "R22") (pin "2") (pinfunction "2_2") (pintype "passive"))
      (node (ref "R27") (pin "2") (pinfunction "2_2") (pintype "passive"))
      (node (ref "R7") (pin "1") (pinfunction "1_1") (pintype "passive"))
      (node (ref "TTL") (pin "2") (pinfunction "2_2") (pintype "passive"))
      (node (ref "TTL-S") (pin "2") (pinfunction "2_2") (pintype "passive"))
      (node (ref "U1") (pin "1") (pinfunction "GND_1") (pintype "passive"))
      (node (ref "U1") (pin "3") (pinfunction "GND_3") (pintype "passive"))
      (node (ref "U4") (pin "2") (pinfunction "GND_2") (pintype "passive"))
      (node (ref "U5") (pin "2") (pinfunction "GND_2") (pintype "passive"))
      (node (ref "U6") (pin "1") (pinfunction "GND_1") (pintype "passive"))
      (node (ref "U6") (pin "3") (pinfunction "GND_3") (pintype "passive"))
    )
    (net (code "93") (name "GNDBAT") (class "Default")
      (node (ref "C10") (pin "2") (pinfunction "2_2") (pintype "passive"))
      (node (ref "C11") (pin "1") (pinfunction "1_1") (pintype "passive"))
      (node (ref "C12") (pin "2") (pinfunction "2_2") (pintype "passive"))
      (node (ref "C13") (pin "1") (pinfunction "1_1") (pintype "passive"))
      (node (ref "C2") (pin "2") (pinfunction "2_2") (pintype "passive"))
      (node (ref "C3") (pin "2") (pinfunction "2_2") (pintype "passive"))
      (node (ref "C4") (pin "2") (pinfunction "2_2") (pintype "passive"))
      (node (ref "C5") (pin "2") (pinfunction "2_2") (pintype "passive"))
      (node (ref "C7") (pin "1") (pinfunction "1_1") (pintype "passive"))
      (node (ref "C8") (pin "2") (pinfunction "2_2") (pintype "passive"))
      (node (ref "C9") (pin "1") (pinfunction "1_1") (pintype "passive"))
      (node (ref "LED5V") (pin "2") (pinfunction "C_2") (pintype "passive"))
      (node (ref "LEDSteer") (pin "2") (pinfunction "C_2") (pintype "passive"))
      (node (ref "Motor_1") (pin "3") (pinfunction "3_3") (pintype "passive"))
      (node (ref "Motor_1") (pin "4") (pinfunction "4_4") (pintype "passive"))
      (node (ref "Motor_2") (pin "3") (pinfunction "3_3") (pintype "passive"))
      (node (ref "Motor_2") (pin "4") (pinfunction "4_4") (pintype "passive"))
      (node (ref "P1") (pin "2") (pinfunction "31_2") (pintype "passive"))
      (node (ref "P2") (pin "2") (pinfunction "31_2") (pintype "passive"))
      (node (ref "R13") (pin "2") (pinfunction "2_2") (pintype "passive"))
      (node (ref "R22") (pin "1") (pinfunction "1_1") (pintype "passive"))
      (node (ref "R4") (pin "1") (pinfunction "1_1") (pintype "passive"))
      (node (ref "Steer") (pin "3") (pinfunction "3_3") (pintype "passive"))
      (node (ref "T型头") (pin "2") (pinfunction "2_2") (pintype "passive"))
      (node (ref "U2") (pin "0") (pinfunction "GND_0") (pintype "passive"))
      (node (ref "U3") (pin "2") (pinfunction "GND_2") (pintype "passive"))
    )
    (net (code "94") (name "GNDCAM") (class "Default")
      (node (ref "C20") (pin "2") (pinfunction "2_2") (pintype "passive"))
      (node (ref "C21") (pin "2") (pinfunction "2_2") (pintype "passive"))
      (node (ref "Camera") (pin "14") (pinfunction "14_14") (pintype "passive"))
      (node (ref "Camera") (pin "4") (pinfunction "4_4") (pintype "passive"))
      (node (ref "LEDCAM") (pin "2") (pinfunction "C_2") (pintype "passive"))
      (node (ref "R7") (pin "2") (pinfunction "2_2") (pintype "passive"))
    )
    (net (code "95") (name "Net-(B-S-Pad1)") (class "Default")
      (node (ref "B-S") (pin "1") (pinfunction "1_1") (pintype "passive"))
      (node (ref "R25") (pin "2") (pinfunction "2_2") (pintype "passive"))
    )
    (net (code "96") (name "Net-(D2-C)") (class "Default")
      (node (ref "C10") (pin "1") (pinfunction "1_1") (pintype "passive"))
      (node (ref "C11") (pin "2") (pinfunction "2_2") (pintype "passive"))
      (node (ref "D2") (pin "2") (pinfunction "C_2") (pintype "passive"))
      (node (ref "U3") (pin "1") (pinfunction "VIN_1") (pintype "passive"))
    )
    (net (code "97") (name "Net-(LED3V3-A)") (class "Default")
      (node (ref "LED3V3") (pin "1") (pinfunction "A_1") (pintype "passive"))
      (node (ref "R11") (pin "2") (pinfunction "2_2") (pintype "passive"))
    )
    (net (code "98") (name "Net-(LED5V-A)") (class "Default")
      (node (ref "LED5V") (pin "1") (pinfunction "A_1") (pintype "passive"))
      (node (ref "R10") (pin "2") (pinfunction "2_2") (pintype "passive"))
    )
    (net (code "99") (name "Net-(LEDCAM-A)") (class "Default")
      (node (ref "LEDCAM") (pin "1") (pinfunction "A_1") (pintype "passive"))
      (node (ref "R12") (pin "2") (pinfunction "2_2") (pintype "passive"))
    )
    (net (code "100") (name "Net-(LEDSteer-A)") (class "Default")
      (node (ref "LEDSteer") (pin "1") (pinfunction "A_1") (pintype "passive"))
      (node (ref "R8") (pin "1") (pinfunction "1_1") (pintype "passive"))
    )
    (net (code "101") (name "Net-(Motor_1-Pad1)") (class "Default")
      (node (ref "Motor_1") (pin "1") (pinfunction "1_1") (pintype "passive"))
      (node (ref "R14") (pin "1") (pinfunction "1_1") (pintype "passive"))
    )
    (net (code "102") (name "Net-(Motor_1-Pad2)") (class "Default")
      (node (ref "Motor_1") (pin "2") (pinfunction "2_2") (pintype "passive"))
      (node (ref "R16") (pin "1") (pinfunction "1_1") (pintype "passive"))
    )
    (net (code "103") (name "Net-(Motor_1-Pad5)") (class "Default")
      (node (ref "Motor_1") (pin "5") (pinfunction "5_5") (pintype "passive"))
      (node (ref "R15") (pin "2") (pinfunction "2_2") (pintype "passive"))
    )
    (net (code "104") (name "Net-(Motor_1-Pad6)") (class "Default")
      (node (ref "Motor_1") (pin "6") (pinfunction "6_6") (pintype "passive"))
      (node (ref "R17") (pin "2") (pinfunction "2_2") (pintype "passive"))
    )
    (net (code "105") (name "Net-(Motor_2-Pad1)") (class "Default")
      (node (ref "Motor_2") (pin "1") (pinfunction "1_1") (pintype "passive"))
      (node (ref "R18") (pin "1") (pinfunction "1_1") (pintype "passive"))
    )
    (net (code "106") (name "Net-(Motor_2-Pad2)") (class "Default")
      (node (ref "Motor_2") (pin "2") (pinfunction "2_2") (pintype "passive"))
      (node (ref "R20") (pin "1") (pinfunction "1_1") (pintype "passive"))
    )
    (net (code "107") (name "Net-(Motor_2-Pad5)") (class "Default")
      (node (ref "Motor_2") (pin "5") (pinfunction "5_5") (pintype "passive"))
      (node (ref "R19") (pin "2") (pinfunction "2_2") (pintype "passive"))
    )
    (net (code "108") (name "Net-(Motor_2-Pad6)") (class "Default")
      (node (ref "Motor_2") (pin "6") (pinfunction "6_6") (pintype "passive"))
      (node (ref "R21") (pin "2") (pinfunction "2_2") (pintype "passive"))
    )
    (net (code "109") (name "Net-(Q1-B)") (class "Default")
      (node (ref "Q1") (pin "1") (pinfunction "B_1") (pintype "passive"))
      (node (ref "R26") (pin "2") (pinfunction "2_2") (pintype "passive"))
    )
    (net (code "110") (name "Net-(Q1-C)") (class "Default")
      (node (ref "B-S") (pin "2") (pinfunction "2_2") (pintype "passive"))
      (node (ref "Q1") (pin "3") (pinfunction "C_3") (pintype "passive"))
    )
    (net (code "111") (name "Net-(R5-Pad1)") (class "Default")
      (node (ref "R5") (pin "1") (pinfunction "1_1") (pintype "passive"))
      (node (ref "R6") (pin "2") (pinfunction "2_2") (pintype "passive"))
    )
    (net (code "112") (name "Net-(R9-Pad2)") (class "Default")
      (node (ref "R9") (pin "2") (pinfunction "2_2") (pintype "passive"))
      (node (ref "Steer") (pin "1") (pinfunction "1_1") (pintype "passive"))
    )
    (net (code "113") (name "Net-(SW1-Pad2)") (class "Default")
      (node (ref "SW1") (pin "2") (pinfunction "2_2") (pintype "passive"))
      (node (ref "T型头") (pin "1") (pinfunction "1_1") (pintype "passive"))
    )
    (net (code "114") (name "Net-(U2-BS)") (class "Default")
      (node (ref "C6") (pin "2") (pinfunction "2_2") (pintype "passive"))
      (node (ref "U2") (pin "1") (pinfunction "BS_1") (pintype "passive"))
    )
    (net (code "115") (name "Net-(U2-EN)") (class "Default")
      (node (ref "R3") (pin "2") (pinfunction "2_2") (pintype "passive"))
      (node (ref "R4") (pin "2") (pinfunction "2_2") (pintype "passive"))
      (node (ref "U2") (pin "3") (pinfunction "EN_3") (pintype "passive"))
    )
    (net (code "116") (name "Net-(U2-LX)") (class "Default")
      (node (ref "C6") (pin "1") (pinfunction "1_1") (pintype "passive"))
      (node (ref "L1") (pin "2") (pinfunction "2_2") (pintype "passive"))
      (node (ref "U2") (pin "2") (pinfunction "LX_2") (pintype "passive"))
    )
    (net (code "117") (name "Net-(U2-SS)") (class "Default")
      (node (ref "C7") (pin "2") (pinfunction "2_2") (pintype "passive"))
      (node (ref "U2") (pin "4") (pinfunction "SS_4") (pintype "passive"))
    )
    (net (code "118") (name "Net-(U2-VCC)") (class "Default")
      (node (ref "C5") (pin "1") (pinfunction "1_1") (pintype "passive"))
      (node (ref "U2") (pin "6") (pinfunction "VCC_6") (pintype "passive"))
    )
    (net (code "119") (name "VCC3V3") (class "Default")
      (node (ref "C16") (pin "1") (pinfunction "1_1") (pintype "passive"))
      (node (ref "C17") (pin "1") (pinfunction "1_1") (pintype "passive"))
      (node (ref "Encoder_1") (pin "2") (pinfunction "2_2") (pintype "passive"))
      (node (ref "Encoder_2") (pin "2") (pinfunction "2_2") (pintype "passive"))
      (node (ref "Encoder_3") (pin "2") (pinfunction "2_2") (pintype "passive"))
      (node (ref "Encoder_4") (pin "2") (pinfunction "2_2") (pintype "passive"))
      (node (ref "GHG") (pin "1") (pinfunction "1_1") (pintype "passive"))
      (node (ref "ICM20602") (pin "1") (pinfunction "1_1") (pintype "passive"))
      (node (ref "OLED-S") (pin "2") (pinfunction "2_2") (pintype "passive"))
      (node (ref "OLED/TFT") (pin "2") (pinfunction "2_2") (pintype "passive"))
      (node (ref "R11") (pin "1") (pinfunction "1_1") (pintype "passive"))
      (node (ref "R25") (pin "1") (pinfunction "1_1") (pintype "passive"))
      (node (ref "R28") (pin "1") (pinfunction "1_1") (pintype "passive"))
      (node (ref "R29") (pin "1") (pinfunction "1_1") (pintype "passive"))
      (node (ref "R30") (pin "1") (pinfunction "1_1") (pintype "passive"))
      (node (ref "R31") (pin "1") (pinfunction "1_1") (pintype "passive"))
      (node (ref "R32") (pin "1") (pinfunction "1_1") (pintype "passive"))
      (node (ref "R33") (pin "1") (pinfunction "1_1") (pintype "passive"))
      (node (ref "U4") (pin "5") (pinfunction "OUT_5") (pintype "passive"))
    )
    (net (code "120") (name "VCC5V") (class "Default")
      (node (ref "C1") (pin "1") (pinfunction "1_1") (pintype "passive"))
      (node (ref "C12") (pin "1") (pinfunction "1_1") (pintype "passive"))
      (node (ref "C13") (pin "2") (pinfunction "2_2") (pintype "passive"))
      (node (ref "C14") (pin "1") (pinfunction "1_1") (pintype "passive"))
      (node (ref "C15") (pin "1") (pinfunction "1_1") (pintype "passive"))
      (node (ref "C18") (pin "1") (pinfunction "1_1") (pintype "passive"))
      (node (ref "C19") (pin "1") (pinfunction "1_1") (pintype "passive"))
      (node (ref "C22") (pin "1") (pinfunction "1_1") (pintype "passive"))
      (node (ref "R10") (pin "1") (pinfunction "1_1") (pintype "passive"))
      (node (ref "TTL") (pin "1") (pinfunction "1_1") (pintype "passive"))
      (node (ref "TTL-S") (pin "1") (pinfunction "1_1") (pintype "passive"))
      (node (ref "U1") (pin "2") (pinfunction "5V_2") (pintype "passive"))
      (node (ref "U3") (pin "3") (pinfunction "VOUT_3") (pintype "passive"))
      (node (ref "U4") (pin "1") (pinfunction "IN_1") (pintype "passive"))
      (node (ref "U4") (pin "3") (pinfunction "EN_3") (pintype "passive"))
      (node (ref "U5") (pin "1") (pinfunction "IN_1") (pintype "passive"))
      (node (ref "U5") (pin "3") (pinfunction "EN_3") (pintype "passive"))
      (node (ref "U6") (pin "2") (pinfunction "5V_2") (pintype "passive"))
    )
    (net (code "121") (name "VCCBAT") (class "Default")
      (node (ref "C2") (pin "1") (pinfunction "1_1") (pintype "passive"))
      (node (ref "C3") (pin "1") (pinfunction "1_1") (pintype "passive"))
      (node (ref "C4") (pin "1") (pinfunction "1_1") (pintype "passive"))
      (node (ref "D2") (pin "1") (pinfunction "A_1") (pintype "passive"))
      (node (ref "P1") (pin "1") (pinfunction "32_1") (pintype "passive"))
      (node (ref "P2") (pin "1") (pinfunction "32_1") (pintype "passive"))
      (node (ref "R3") (pin "1") (pinfunction "1_1") (pintype "passive"))
      (node (ref "SW1") (pin "3") (pinfunction "3_3") (pintype "passive"))
      (node (ref "U2") (pin "7") (pinfunction "VIN_7") (pintype "passive"))
      (node (ref "U2") (pin "8") (pinfunction "VIN_8") (pintype "passive"))
    )
    (net (code "122") (name "VCCCAM") (class "Default")
      (node (ref "C20") (pin "1") (pinfunction "1_1") (pintype "passive"))
      (node (ref "C21") (pin "1") (pinfunction "1_1") (pintype "passive"))
      (node (ref "Camera") (pin "16") (pinfunction "16_16") (pintype "passive"))
      (node (ref "R12") (pin "1") (pinfunction "1_1") (pintype "passive"))
      (node (ref "U5") (pin "5") (pinfunction "OUT_5") (pintype "passive"))
    )
    (net (code "123") (name "VCCSteer") (class "Default")
      (node (ref "C8") (pin "1") (pinfunction "1_1") (pintype "passive"))
      (node (ref "C9") (pin "2") (pinfunction "2_2") (pintype "passive"))
      (node (ref "L1") (pin "1") (pinfunction "1_1") (pintype "passive"))
      (node (ref "R5") (pin "2") (pinfunction "2_2") (pintype "passive"))
      (node (ref "R8") (pin "2") (pinfunction "2_2") (pintype "passive"))
      (node (ref "Steer") (pin "2") (pinfunction "2_2") (pintype "passive"))
    )
    (net (code "124") (name "unconnected-(Camera-Pad10)") (class "Default")
      (node (ref "Camera") (pin "10") (pinfunction "10_10") (pintype "passive+no_connect"))
    )
    (net (code "125") (name "unconnected-(ICM20602-Pad7)") (class "Default")
      (node (ref "ICM20602") (pin "7") (pinfunction "7_7") (pintype "passive+no_connect"))
    )
    (net (code "126") (name "unconnected-(ICM20602-Pad8)") (class "Default")
      (node (ref "ICM20602") (pin "8") (pinfunction "8_8") (pintype "passive+no_connect"))
    )
    (net (code "127") (name "unconnected-(M1-Pad1)") (class "Default")
      (node (ref "M1") (pin "1") (pinfunction "1_1") (pintype "passive+no_connect"))
    )
    (net (code "128") (name "unconnected-(M2-Pad1)") (class "Default")
      (node (ref "M2") (pin "1") (pinfunction "1_1") (pintype "passive+no_connect"))
    )
    (net (code "129") (name "unconnected-(M3-Pad1)") (class "Default")
      (node (ref "M3") (pin "1") (pinfunction "1_1") (pintype "passive+no_connect"))
    )
    (net (code "130") (name "unconnected-(M4-Pad1)") (class "Default")
      (node (ref "M4") (pin "1") (pinfunction "1_1") (pintype "passive+no_connect"))
    )
    (net (code "131") (name "unconnected-(M5-Pad1)") (class "Default")
      (node (ref "M5") (pin "1") (pinfunction "1_1") (pintype "passive+no_connect"))
    )
    (net (code "132") (name "unconnected-(OLED-S-Pad8)") (class "Default")
      (node (ref "OLED-S") (pin "8") (pinfunction "8_8") (pintype "passive+no_connect"))
    )
    (net (code "133") (name "unconnected-(OLED/TFT-Pad8)") (class "Default")
      (node (ref "OLED/TFT") (pin "8") (pinfunction "8_8") (pintype "passive+no_connect"))
    )
    (net (code "134") (name "unconnected-(R6-Pad3)") (class "Default")
      (node (ref "R6") (pin "3") (pinfunction "3_3") (pintype "passive"))
    )
    (net (code "135") (name "unconnected-(SW1-Pad1)") (class "Default")
      (node (ref "SW1") (pin "1") (pinfunction "1_1") (pintype "passive+no_connect"))
    )
    (net (code "136") (name "unconnected-(U1-3V3-Pad4)") (class "Default")
      (node (ref "U1") (pin "4") (pinfunction "3V3_4") (pintype "passive+no_connect"))
    )
    (net (code "137") (name "unconnected-(U1-3V3-Pad6)") (class "Default")
      (node (ref "U1") (pin "6") (pinfunction "3V3_6") (pintype "passive+no_connect"))
    )
    (net (code "138") (name "unconnected-(U4-NC-Pad4)") (class "Default")
      (node (ref "U4") (pin "4") (pinfunction "NC_4") (pintype "passive+no_connect"))
    )
    (net (code "139") (name "unconnected-(U5-NC-Pad4)") (class "Default")
      (node (ref "U5") (pin "4") (pinfunction "NC_4") (pintype "passive+no_connect"))
    )
    (net (code "140") (name "unconnected-(U6-3V3-Pad4)") (class "Default")
      (node (ref "U6") (pin "4") (pinfunction "3V3_4") (pintype "passive+no_connect"))
    )
    (net (code "141") (name "unconnected-(U6-3V3-Pad6)") (class "Default")
      (node (ref "U6") (pin "6") (pinfunction "3V3_6") (pintype "passive+no_connect"))
    )
  )
)
